# ProPrj_ADX_IDCtoPinheader_adapter_2026-0.net
KiCad netlist of a schematic drawn in EasyEDA Pro
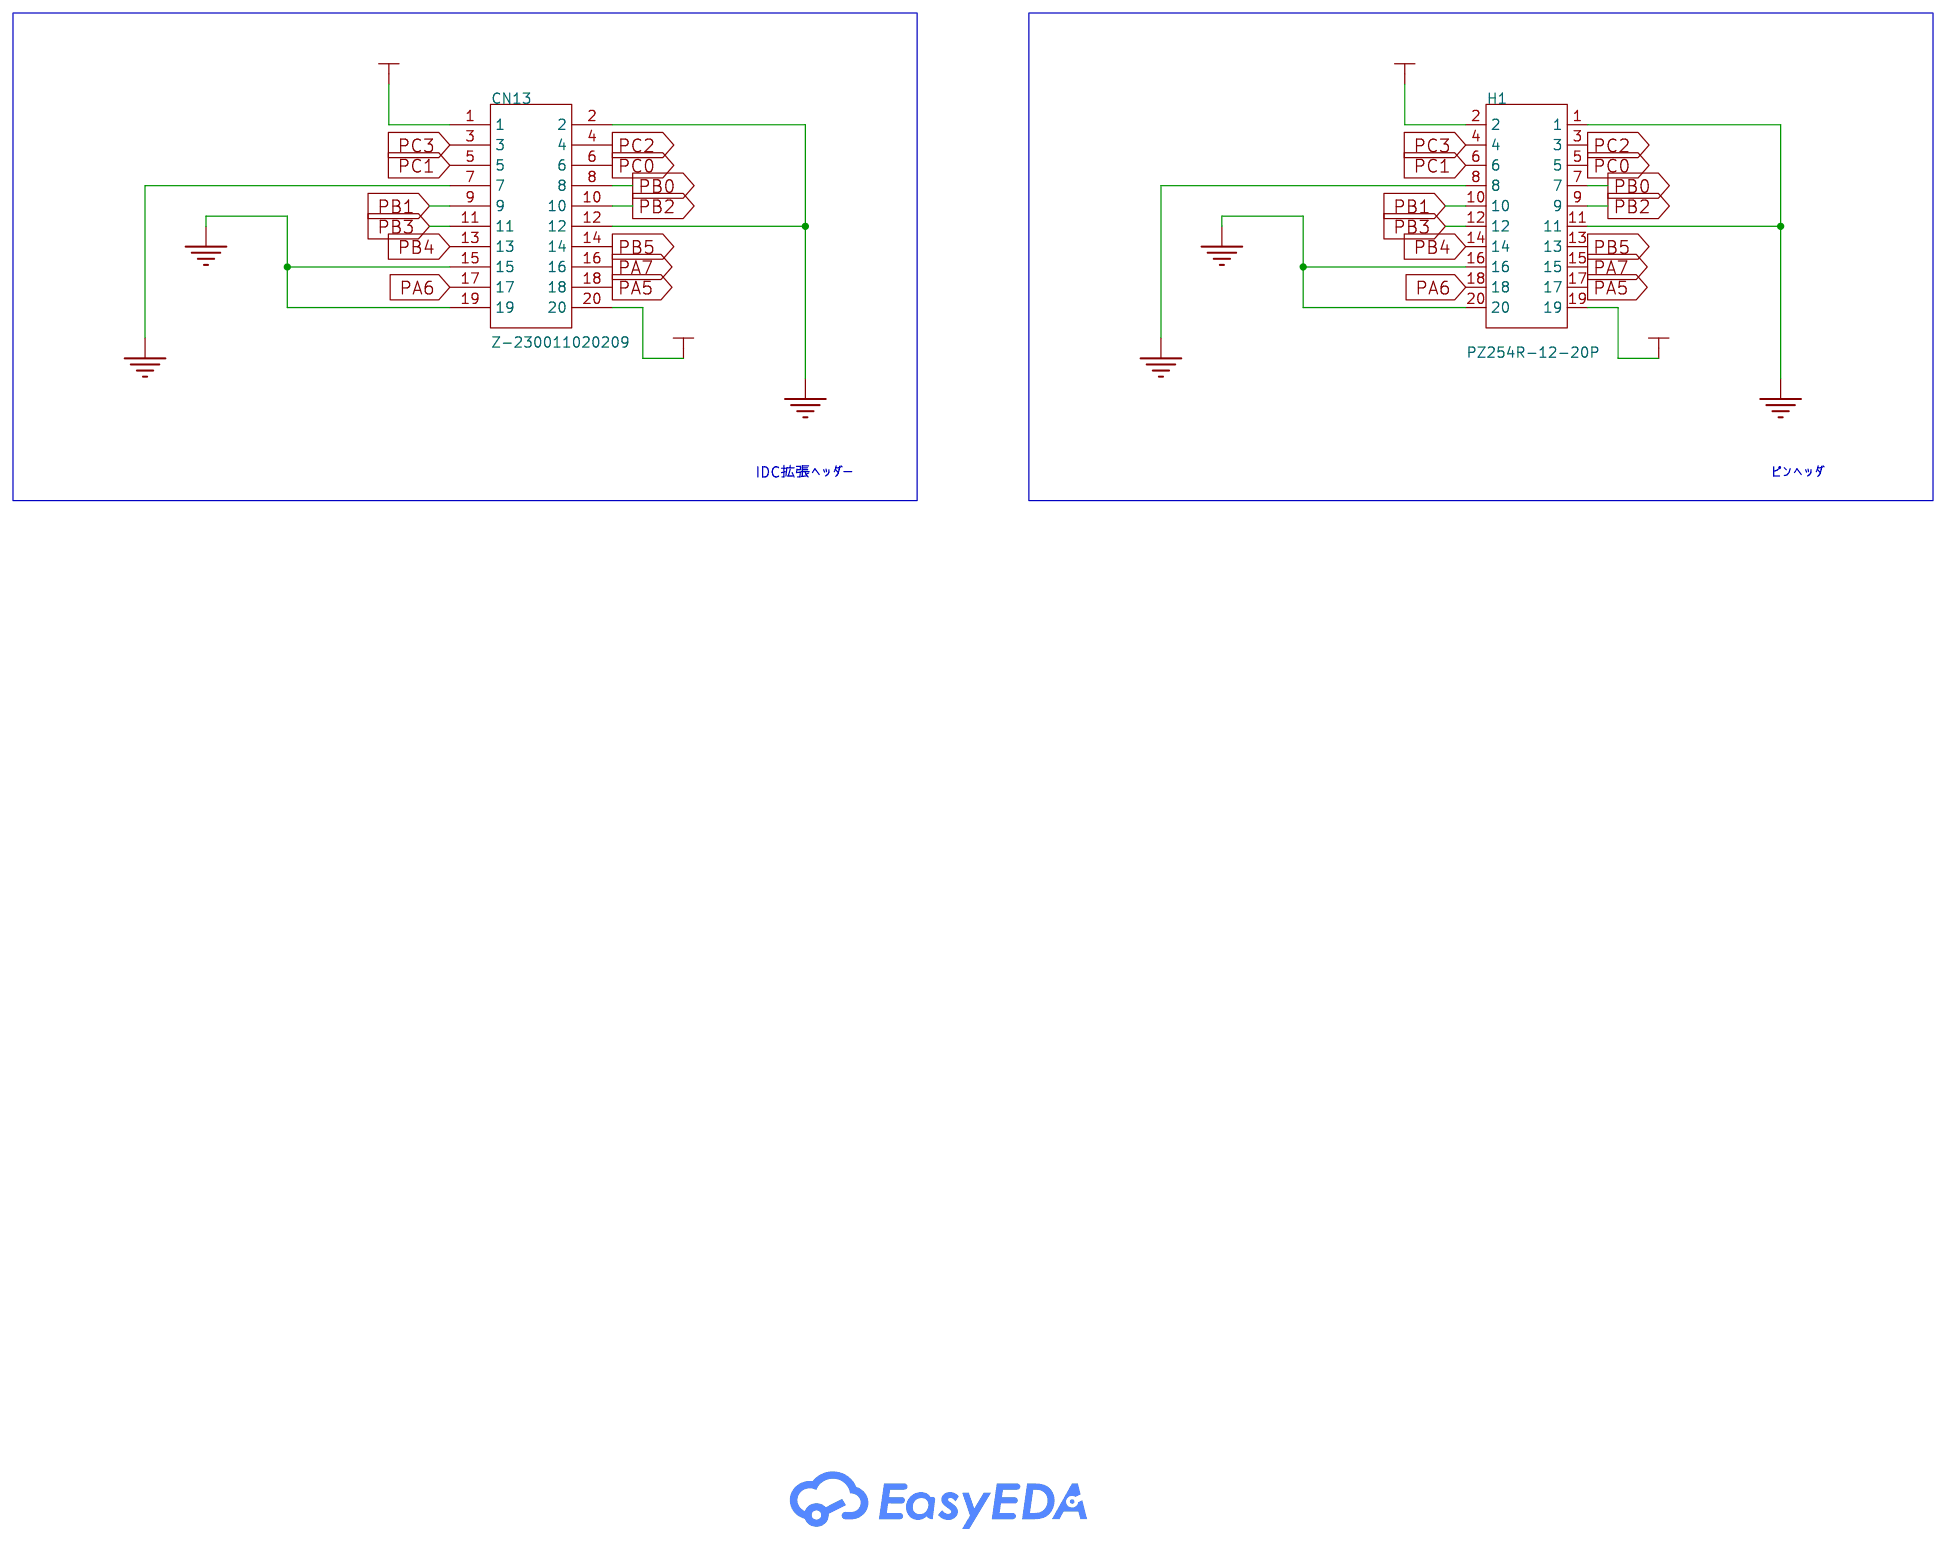
[diagram p0: schematic sheet]

(export (version "E")
  (design (tool "Eeschema 10.0.6"))
  (components
    (comp (ref "CN13")
      (value "Z-230011020209")
      (footprint "easyedapro:IDC-TH_20P-P2.54_Z-230011020209")
      (fields (field (name "Manufacturer") "Nextron(正凌)"))
      (libsource (lib "easyedapro") (part "Z-230011020209"))
    )
    (comp (ref "H1")
      (value "PZ254R-12-20P")
      (footprint "easyedapro:HDR-TH_20P-P2.54-H-M-R2-C10-S2.54")
      (fields (field (name "Manufacturer") "XFCN(兴飞)"))
      (libsource (lib "easyedapro") (part "PZ254R-12-20P"))
    )
  )
  (nets
    (net (code "1") (name "GND_5V") (class "Default")
      (node (ref "CN13") (pin "12") (pinfunction "12_12") (pintype "input"))
      (node (ref "CN13") (pin "15") (pinfunction "15_15") (pintype "input"))
      (node (ref "CN13") (pin "19") (pinfunction "19_19") (pintype "input"))
      (node (ref "CN13") (pin "2") (pinfunction "2_2") (pintype "input"))
      (node (ref "CN13") (pin "7") (pinfunction "7_7") (pintype "input"))
      (node (ref "H1") (pin "1") (pinfunction "1_1") (pintype "unspecified"))
      (node (ref "H1") (pin "11") (pinfunction "11_11") (pintype "unspecified"))
      (node (ref "H1") (pin "16") (pinfunction "16_16") (pintype "unspecified"))
      (node (ref "H1") (pin "20") (pinfunction "20_20") (pintype "unspecified"))
      (node (ref "H1") (pin "8") (pinfunction "8_8") (pintype "unspecified"))
    )
    (net (code "2") (name "PA5") (class "Default")
      (node (ref "CN13") (pin "18") (pinfunction "18_18") (pintype "input"))
      (node (ref "H1") (pin "17") (pinfunction "17_17") (pintype "unspecified"))
    )
    (net (code "3") (name "PA6") (class "Default")
      (node (ref "CN13") (pin "17") (pinfunction "17_17") (pintype "input"))
      (node (ref "H1") (pin "18") (pinfunction "18_18") (pintype "unspecified"))
    )
    (net (code "4") (name "PA7") (class "Default")
      (node (ref "CN13") (pin "16") (pinfunction "16_16") (pintype "input"))
      (node (ref "H1") (pin "15") (pinfunction "15_15") (pintype "unspecified"))
    )
    (net (code "5") (name "PB0") (class "Default")
      (node (ref "CN13") (pin "8") (pinfunction "8_8") (pintype "input"))
      (node (ref "H1") (pin "7") (pinfunction "7_7") (pintype "unspecified"))
    )
    (net (code "6") (name "PB1") (class "Default")
      (node (ref "CN13") (pin "9") (pinfunction "9_9") (pintype "input"))
      (node (ref "H1") (pin "10") (pinfunction "10_10") (pintype "unspecified"))
    )
    (net (code "7") (name "PB2") (class "Default")
      (node (ref "CN13") (pin "10") (pinfunction "10_10") (pintype "input"))
      (node (ref "H1") (pin "9") (pinfunction "9_9") (pintype "unspecified"))
    )
    (net (code "8") (name "PB3") (class "Default")
      (node (ref "CN13") (pin "11") (pinfunction "11_11") (pintype "input"))
      (node (ref "H1") (pin "12") (pinfunction "12_12") (pintype "unspecified"))
    )
    (net (code "9") (name "PB4") (class "Default")
      (node (ref "CN13") (pin "13") (pinfunction "13_13") (pintype "input"))
      (node (ref "H1") (pin "14") (pinfunction "14_14") (pintype "unspecified"))
    )
    (net (code "10") (name "PB5") (class "Default")
      (node (ref "CN13") (pin "14") (pinfunction "14_14") (pintype "input"))
      (node (ref "H1") (pin "13") (pinfunction "13_13") (pintype "unspecified"))
    )
    (net (code "11") (name "PC0") (class "Default")
      (node (ref "CN13") (pin "6") (pinfunction "6_6") (pintype "input"))
      (node (ref "H1") (pin "5") (pinfunction "5_5") (pintype "unspecified"))
    )
    (net (code "12") (name "PC1") (class "Default")
      (node (ref "CN13") (pin "5") (pinfunction "5_5") (pintype "input"))
      (node (ref "H1") (pin "6") (pinfunction "6_6") (pintype "unspecified"))
    )
    (net (code "13") (name "PC2") (class "Default")
      (node (ref "CN13") (pin "4") (pinfunction "4_4") (pintype "input"))
      (node (ref "H1") (pin "3") (pinfunction "3_3") (pintype "unspecified"))
    )
    (net (code "14") (name "PC3") (class "Default")
      (node (ref "CN13") (pin "3") (pinfunction "3_3") (pintype "input"))
      (node (ref "H1") (pin "4") (pinfunction "4_4") (pintype "unspecified"))
    )
    (net (code "15") (name "VDD1") (class "Default")
      (node (ref "CN13") (pin "1") (pinfunction "1_1") (pintype "input"))
      (node (ref "H1") (pin "2") (pinfunction "2_2") (pintype "unspecified"))
    )
    (net (code "16") (name "VDD2") (class "Default")
      (node (ref "CN13") (pin "20") (pinfunction "20_20") (pintype "input"))
      (node (ref "H1") (pin "19") (pinfunction "19_19") (pintype "unspecified"))
    )
  )
)
